# LMH.net
KiCad netlist of a schematic drawn in Altium Designer
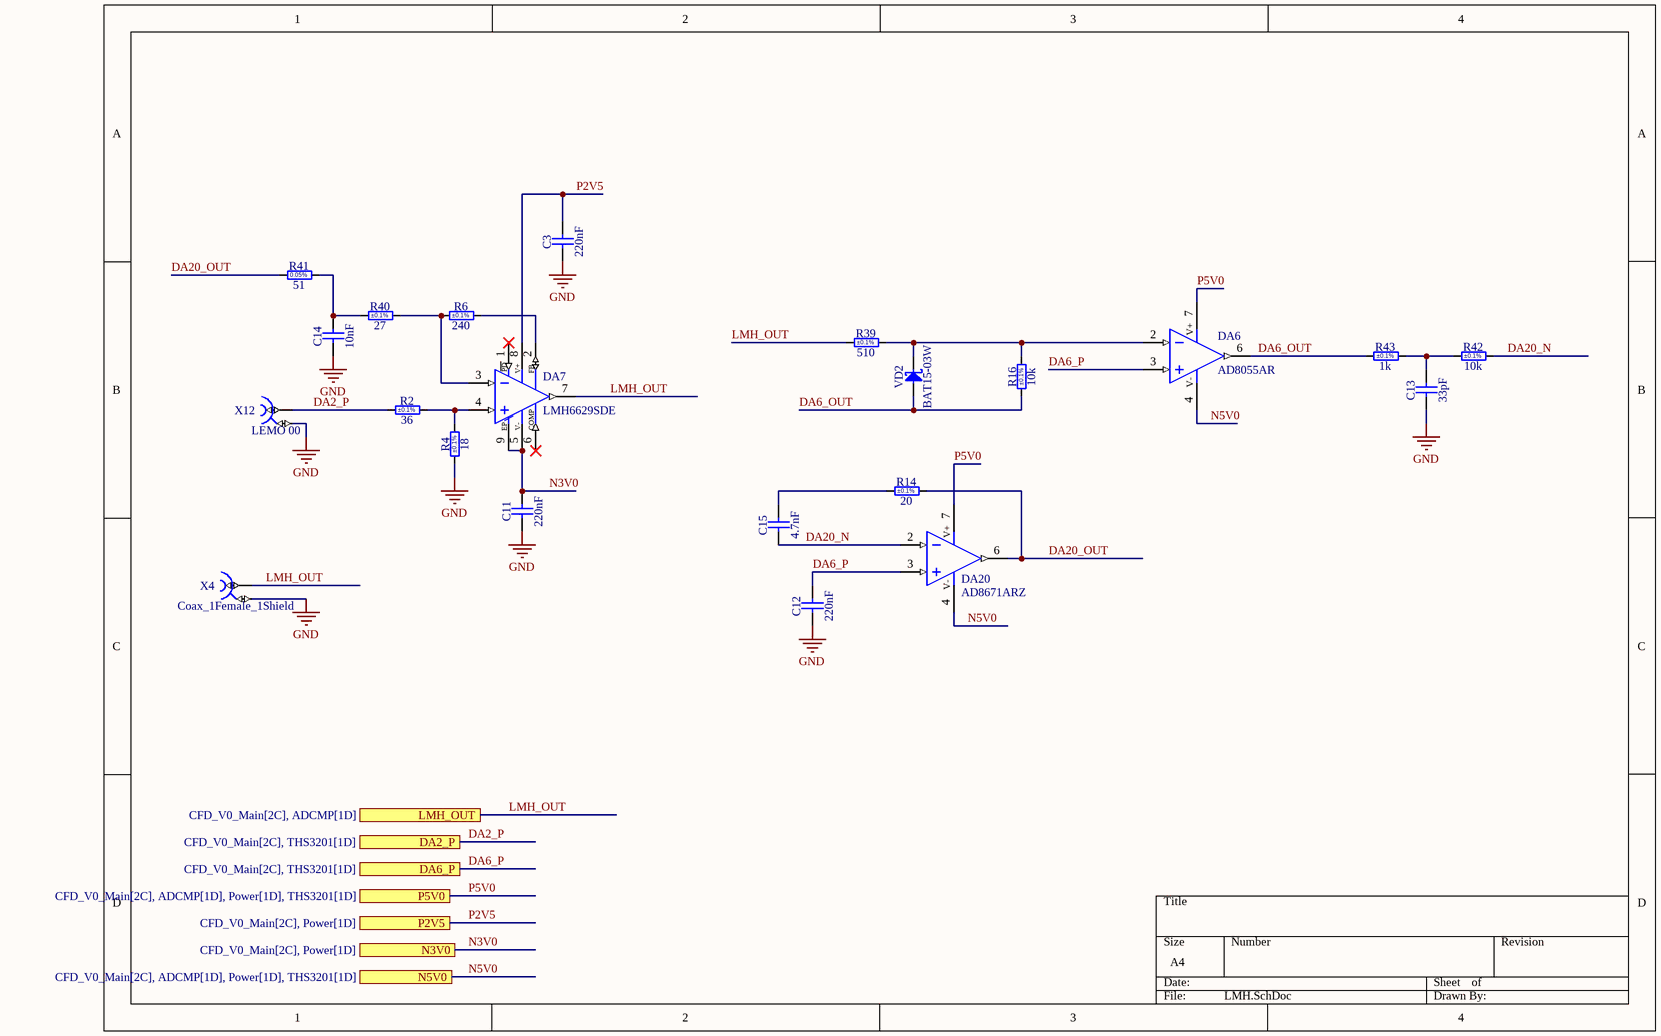
[diagram p0: LMH.SchDoc]

(export (version "E")
  (design (tool "Eeschema 10.0.6"))
  (components
    (comp (ref "C3")
      (value "220nF")
      (footprint "CAPC2012X135N")
      (description "Non-polarised capacitor")
      (fields
        (field (name "PART NUMBER") "CC0805_220NF_50V_10%_X7R")
        (field (name "VOLTAGE") "50V")
        (field (name "AUTHOR") "CERN DEM JLC")
      )
      (libsource (lib "Capacitors") (part "Capacitor - non polarized"))
    )
    (comp (ref "C11")
      (value "220nF")
      (footprint "CAPC2012X135N")
      (description "Non-polarised capacitor")
      (fields
        (field (name "PART NUMBER") "CC0805_220NF_50V_10%_X7R")
        (field (name "VOLTAGE") "50V")
        (field (name "AUTHOR") "CERN DEM JLC")
      )
      (libsource (lib "Capacitors") (part "Capacitor - non polarized"))
    )
    (comp (ref "C12")
      (value "220nF")
      (footprint "CAPC2012X135N")
      (description "Non-polarised capacitor")
      (fields
        (field (name "PART NUMBER") "CC0805_220NF_50V_10%_X7R")
        (field (name "VOLTAGE") "50V")
        (field (name "AUTHOR") "CERN DEM JLC")
      )
      (libsource (lib "Capacitors") (part "Capacitor - non polarized"))
    )
    (comp (ref "C13")
      (value "33pF")
      (footprint "CAPC2013X115N")
      (description "Non-polarised capacitor")
      (fields
        (field (name "PART NUMBER") "CC0805_33PF_200V_1%_NP0")
        (field (name "VOLTAGE") "200V")
        (field (name "AUTHOR") "CERN DEM HF")
      )
      (libsource (lib "Capacitors") (part "Capacitor - non polarized"))
    )
    (comp (ref "C14")
      (value "10nF")
      (footprint "CAPC2012X135N")
      (description "Non-polarised capacitor")
      (fields
        (field (name "PART NUMBER") "CC0805_10NF_50V_2%_C0G")
        (field (name "VOLTAGE") "50V")
        (field (name "AUTHOR") "CERN DEM HF")
      )
      (libsource (lib "Capacitors") (part "Capacitor - non polarized"))
    )
    (comp (ref "C15")
      (value "4.7nF")
      (footprint "CAPC2012X135N")
      (description "Non-polarised capacitor")
      (fields
        (field (name "PART NUMBER") "CC0805_4.7NF_250V_1%_NP0")
        (field (name "VOLTAGE") "250V")
        (field (name "AUTHOR") "CERN DEM HF")
      )
      (libsource (lib "Capacitors") (part "Capacitor - non polarized"))
    )
    (comp (ref "DA6")
      (value "AD8055AR")
      (footprint "SOIC127P600X175-8N")
      (description "Operational Amplifier")
      (fields (field (name "MANUFACTURER") "ANALOG DEVICES") (field (name "AUTHOR") "CERN DEM HF"))
      (libsource (lib "ICs And Semiconductors") (part "Operational Amplifier Type1"))
    )
    (comp (ref "DA7")
      (value "LMH6629SDE")
      (footprint "TEXAS_NGQ0008A")
      (description "Ultra-Low Noise, High-Speed Operational Amplifier with Shutdown")
      (fields (field (name "MANUFACTURER") "TEXAS INSTRUMENTS") (field (name "AUTHOR") "CERN DEM HF"))
      (libsource (lib "ICs And Semiconductors") (part "LMH6629SDE"))
    )
    (comp (ref "DA20")
      (value "AD8671ARZ")
      (footprint "SOIC127P600X175-8N")
      (description "Operational Amplifier")
      (fields
        (field (name "MANUFACTURER") "ANALOG DEVICES")
        (field (name "MANUFACTURER PART NUMBER") "AD8671AR")
        (field (name "AUTHOR") "CERN DEM JLC")
      )
      (libsource (lib "ICs And Semiconductors") (part "Operational Amplifier Type1"))
    )
    (comp (ref "R2")
      (value "36")
      (footprint "RESC1608X64N")
      (description "Resistor - 0.1%")
      (fields
        (field (name "TOLERANCE") "±0.1%")
        (field (name "PART NUMBER") "R0603_36R_0.1%_0.1W_10PPM")
        (field (name "POWER") "0.1W")
        (field (name "AUTHOR") "CERN DEM HF")
      )
      (libsource (lib "Resistors") (part "Resistor - 0.1%"))
    )
    (comp (ref "R4")
      (value "18")
      (footprint "RESC1608X64N")
      (description "Resistor - 0.1%")
      (fields
        (field (name "TOLERANCE") "±0.1%")
        (field (name "PART NUMBER") "R0603_18R_0.1%_0.1W_25PPM")
        (field (name "POWER") "0.1W")
        (field (name "AUTHOR") "CERN DEM HF")
      )
      (libsource (lib "Resistors") (part "Resistor - 0.1%"))
    )
    (comp (ref "R6")
      (value "240")
      (footprint "RESC1005X40N")
      (description "Resistor - 0.1%")
      (fields
        (field (name "TOLERANCE") "±0.1%")
        (field (name "PART NUMBER") "R0402_240R_0.1%_0.0625W_10PPM")
        (field (name "POWER") "0.063W")
        (field (name "AUTHOR") "CERN DEM HF")
      )
      (libsource (lib "Resistors") (part "Resistor - 0.1%"))
    )
    (comp (ref "R14")
      (value "20")
      (footprint "RESC2012X60N")
      (description "Resistor - 0.1%")
      (fields
        (field (name "TOLERANCE") "±0.1%")
        (field (name "PART NUMBER") "R0805_20R_0.1%_0.1W_10PPM")
        (field (name "POWER") "0.1W")
        (field (name "AUTHOR") "CERN DEM JLC")
      )
      (libsource (lib "Resistors") (part "Resistor - 0.1%"))
    )
    (comp (ref "R16")
      (value "10k")
      (footprint "RESC2012X60N")
      (description "Resistor - 0.1%")
      (fields
        (field (name "TOLERANCE") "±0.1%")
        (field (name "PART NUMBER") "R0805_10K_0.1%_0.1W_10PPM")
        (field (name "POWER") "0.1W")
        (field (name "AUTHOR") "CERN DEM JLC")
      )
      (libsource (lib "Resistors") (part "Resistor - 0.1%"))
    )
    (comp (ref "R39")
      (value "510")
      (footprint "RESC1005X40N")
      (description "Resistor - 0.1%")
      (fields
        (field (name "TOLERANCE") "±0.1%")
        (field (name "PART NUMBER") "R0402_510R_0.1%_0.0625W_10PPM")
        (field (name "POWER") "0.063W")
        (field (name "AUTHOR") "CERN DEM HF")
      )
      (libsource (lib "Resistors") (part "Resistor - 0.1%"))
    )
    (comp (ref "R40")
      (value "27")
      (footprint "RESC1608X64N")
      (description "Resistor - 0.1%")
      (fields
        (field (name "TOLERANCE") "±0.1%")
        (field (name "PART NUMBER") "R0603_27R_0.1%_0.1W_10PPM")
        (field (name "POWER") "0.1W")
        (field (name "AUTHOR") "CERN DEM HF")
      )
      (libsource (lib "Resistors") (part "Resistor - 0.1%"))
    )
    (comp (ref "R41")
      (value "51")
      (footprint "RESC2012X60N")
      (description "Resistor - 0.05%")
      (fields
        (field (name "PART NUMBER") "R0805_51R_0.05%_0.125W_10PPM")
        (field (name "POWER") "0.1W")
        (field (name "AUTHOR") "CERN DEM HF")
      )
      (libsource (lib "Resistors") (part "Resistor - 0.05%"))
    )
    (comp (ref "R42")
      (value "10k")
      (footprint "RESC2012X60N")
      (description "Resistor - 0.1%")
      (fields
        (field (name "TOLERANCE") "±0.1%")
        (field (name "PART NUMBER") "R0805_10K_0.1%_0.1W_10PPM")
        (field (name "POWER") "0.1W")
        (field (name "AUTHOR") "CERN DEM JLC")
      )
      (libsource (lib "Resistors") (part "Resistor - 0.1%"))
    )
    (comp (ref "R43")
      (value "1k")
      (footprint "RESC2012X60N")
      (description "Resistor - 0.1%")
      (fields
        (field (name "TOLERANCE") "±0.1%")
        (field (name "PART NUMBER") "R0805_1K_0.1%_0.1W_10PPM")
        (field (name "POWER") "0.1W")
        (field (name "AUTHOR") "CERN DEM JLC")
      )
      (libsource (lib "Resistors") (part "Resistor - 0.1%"))
    )
    (comp (ref "VD2")
      (value "BAT15-03W")
      (footprint "SOD2512X110N")
      (description "Schottky Diode")
      (fields
        (field (name "VOLTAGE") "4V")
        (field (name "POWER") "100mA")
        (field (name "AUTHOR") "CERN DEM HF")
      )
      (libsource (lib "ICs And Semiconductors") (part "Diode Schottky"))
    )
    (comp (ref "X4")
      (value "Coax_1Female_1Shield")
      (footprint "SAMTEC_MMCX-J-P-H-ST-TH1")
      (fields
        (field (name "PART NUMBER") "SAMTEC_MMCX-J-P-H-ST-TH1")
        (field (name "MANUFACTURER") "SAMTEC")
        (field (name "MANUFACTURER PART NUMBER") "MMCX-J-P-H-ST-TH1")
        (field (name "AUTHOR") "CERN DEM JLC")
      )
      (libsource (lib "Connectors") (part "Coax_1Female_1Shield"))
    )
    (comp (ref "X12")
      (value "LEMO 00")
      (footprint "LEMO_EPL.00.250.NTN")
      (fields
        (field (name "PART NUMBER") "LEMO_EPL.00.250.NTN")
        (field (name "MANUFACTURER") "LEMO")
        (field (name "MANUFACTURER PART NUMBER") "EPL.00.250.NTN")
        (field (name "AUTHOR") "CERN DEM JLC")
      )
      (libsource (lib "Connectors") (part "Coax_1Female_1Shield"))
    )
  )
  (nets
    (net (code "1") (name "/DA2_P") (class "Default")
      (node (ref "R2") (pin "1") (pinfunction "1_1") (pintype "passive"))
      (node (ref "X12") (pin "1") (pinfunction "1_1") (pintype "bidirectional"))
    )
    (net (code "2") (name "/DA6_OUT") (class "Default")
      (node (ref "DA6") (pin "6") (pinfunction "OUT_6") (pintype "output"))
      (node (ref "R16") (pin "1") (pinfunction "1_1") (pintype "passive"))
      (node (ref "R43") (pin "1") (pinfunction "1_1") (pintype "passive"))
      (node (ref "VD2") (pin "2") (pinfunction "A_2") (pintype "passive"))
    )
    (net (code "3") (name "/DA6_P") (class "Default")
      (node (ref "C12") (pin "2") (pinfunction "2_2") (pintype "passive"))
      (node (ref "DA20") (pin "3") (pinfunction "IN+_3") (pintype "input"))
      (node (ref "DA6") (pin "3") (pinfunction "IN+_3") (pintype "input"))
    )
    (net (code "4") (name "/DA20_N") (class "Default")
      (node (ref "C15") (pin "1") (pinfunction "1_1") (pintype "passive"))
      (node (ref "DA20") (pin "2") (pinfunction "IN-_2") (pintype "input"))
      (node (ref "R42") (pin "2") (pinfunction "2_2") (pintype "passive"))
    )
    (net (code "5") (name "/DA20_OUT") (class "Default")
      (node (ref "DA20") (pin "6") (pinfunction "OUT_6") (pintype "output"))
      (node (ref "R14") (pin "2") (pinfunction "2_2") (pintype "passive"))
      (node (ref "R41") (pin "1") (pinfunction "1_1") (pintype "passive"))
    )
    (net (code "6") (name "/LMH_OUT") (class "Default")
      (node (ref "DA7") (pin "7") (pinfunction "OUT_7") (pintype "output"))
      (node (ref "R39") (pin "1") (pinfunction "1_1") (pintype "passive"))
      (node (ref "X4") (pin "1") (pinfunction "1_1") (pintype "bidirectional"))
    )
    (net (code "7") (name "/N3V0") (class "Default")
      (node (ref "C11") (pin "2") (pinfunction "2_2") (pintype "passive"))
      (node (ref "DA7") (pin "5") (pinfunction "V-_5") (pintype "power_in"))
      (node (ref "DA7") (pin "9") (pinfunction "EP_9") (pintype "power_in"))
    )
    (net (code "8") (name "/N5V0") (class "Default")
      (node (ref "DA20") (pin "4") (pinfunction "V-_4") (pintype "power_in"))
      (node (ref "DA6") (pin "4") (pinfunction "V-_4") (pintype "power_in"))
    )
    (net (code "9") (name "/P2V5") (class "Default")
      (node (ref "C3") (pin "2") (pinfunction "2_2") (pintype "passive"))
      (node (ref "DA7") (pin "8") (pinfunction "V+_8") (pintype "power_in"))
    )
    (net (code "10") (name "/P5V0") (class "Default")
      (node (ref "DA20") (pin "7") (pinfunction "V+_7") (pintype "power_in"))
      (node (ref "DA6") (pin "7") (pinfunction "V+_7") (pintype "power_in"))
    )
    (net (code "11") (name "GND") (class "Default")
      (node (ref "C11") (pin "1") (pinfunction "1_1") (pintype "passive"))
      (node (ref "C12") (pin "1") (pinfunction "1_1") (pintype "passive"))
      (node (ref "C13") (pin "1") (pinfunction "1_1") (pintype "passive"))
      (node (ref "C14") (pin "1") (pinfunction "1_1") (pintype "passive"))
      (node (ref "C3") (pin "1") (pinfunction "1_1") (pintype "passive"))
      (node (ref "R4") (pin "1") (pinfunction "1_1") (pintype "passive"))
      (node (ref "X12") (pin "2") (pinfunction "2_2") (pintype "bidirectional"))
      (node (ref "X4") (pin "2") (pinfunction "2_2") (pintype "bidirectional"))
    )
    (net (code "12") (name "Net-(C13-Pad2)") (class "Default")
      (node (ref "C13") (pin "2") (pinfunction "2_2") (pintype "passive"))
      (node (ref "R42") (pin "1") (pinfunction "1_1") (pintype "passive"))
      (node (ref "R43") (pin "2") (pinfunction "2_2") (pintype "passive"))
    )
    (net (code "13") (name "Net-(C14-Pad2)") (class "Default")
      (node (ref "C14") (pin "2") (pinfunction "2_2") (pintype "passive"))
      (node (ref "R40") (pin "1") (pinfunction "1_1") (pintype "passive"))
      (node (ref "R41") (pin "2") (pinfunction "2_2") (pintype "passive"))
    )
    (net (code "14") (name "Net-(C15-Pad2)") (class "Default")
      (node (ref "C15") (pin "2") (pinfunction "2_2") (pintype "passive"))
      (node (ref "R14") (pin "1") (pinfunction "1_1") (pintype "passive"))
    )
    (net (code "15") (name "Net-(DA6-IN-)") (class "Default")
      (node (ref "DA6") (pin "2") (pinfunction "IN-_2") (pintype "input"))
      (node (ref "R16") (pin "2") (pinfunction "2_2") (pintype "passive"))
      (node (ref "R39") (pin "2") (pinfunction "2_2") (pintype "passive"))
      (node (ref "VD2") (pin "1") (pinfunction "C_1") (pintype "passive"))
    )
    (net (code "16") (name "Net-(DA7-FB)") (class "Default")
      (node (ref "DA7") (pin "2") (pinfunction "FB_2") (pintype "bidirectional"))
      (node (ref "R6") (pin "2") (pinfunction "2_2") (pintype "passive"))
    )
    (net (code "17") (name "Net-(DA7-IN+)") (class "Default")
      (node (ref "DA7") (pin "4") (pinfunction "IN+_4") (pintype "input"))
      (node (ref "R2") (pin "2") (pinfunction "2_2") (pintype "passive"))
      (node (ref "R4") (pin "2") (pinfunction "2_2") (pintype "passive"))
    )
    (net (code "18") (name "Net-(DA7-IN-)") (class "Default")
      (node (ref "DA7") (pin "3") (pinfunction "IN-_3") (pintype "input"))
      (node (ref "R40") (pin "2") (pinfunction "2_2") (pintype "passive"))
      (node (ref "R6") (pin "1") (pinfunction "1_1") (pintype "passive"))
    )
    (net (code "19") (name "unconnected-(DA7-COMP-Pad6)") (class "Default")
      (node (ref "DA7") (pin "6") (pinfunction "COMP_6") (pintype "input+no_connect"))
    )
    (net (code "20") (name "unconnected-(DA7-~{PD}-Pad1)") (class "Default")
      (node (ref "DA7") (pin "1") (pinfunction "~{PD}_1") (pintype "input+no_connect"))
    )
  )
)
